# mcu.net
KiCad netlist of a schematic drawn in Altium Designer
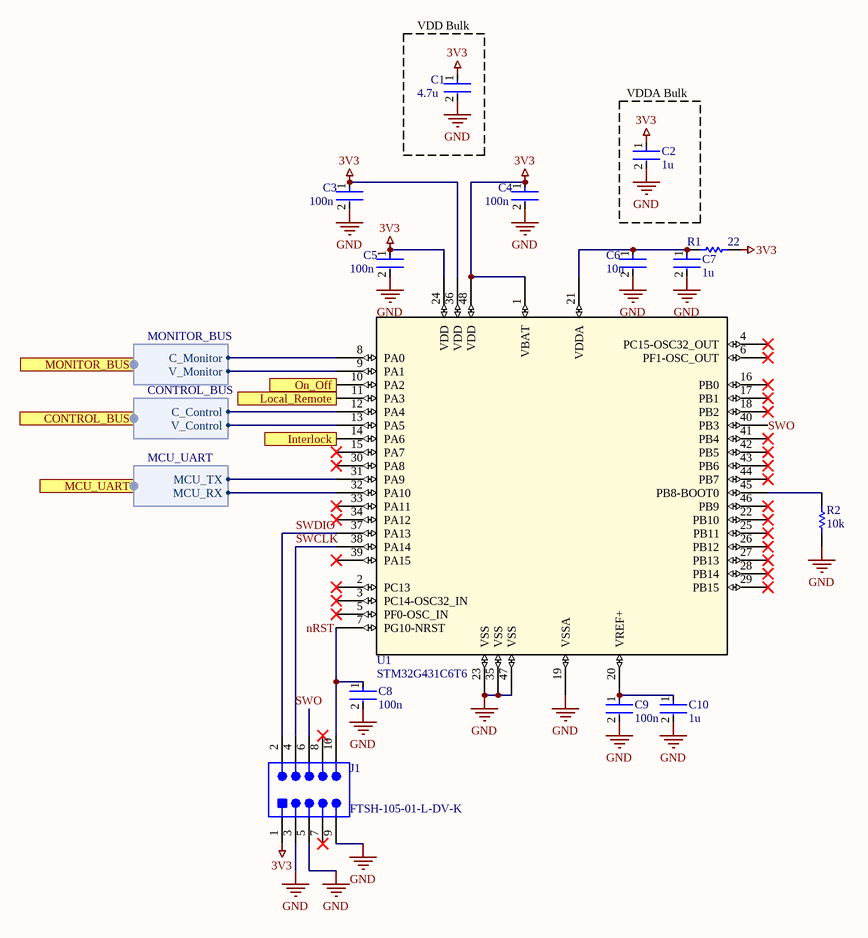
[diagram p0: mcu.SchDoc]

(export (version "E")
  (design (tool "Eeschema 10.0.6"))
  (components
    (comp (ref "C1")
      (value "4.7u")
      (footprint "C_IM 0805")
      (description "Surface Mount Ceramic Multilayer Capacitor 4.7uF 10% X5R 6.3V 0805 Blister T/R")
      (fields
        (field (name "MANUFACTURER") "Yageo Group")
        (field (name "MANUFACTURER PART NUMBER") "CC0805KKX5R5BB475")
      )
      (libsource (lib "Schlib1") (part "CC0805KKX5R5BB475"))
    )
    (comp (ref "C2")
      (value "1u")
      (footprint "C_IM 0603")
      (description "6.3V 1uF X5R ±20% 0603 Multilayer Ceramic Capacitors MLCC - SMD/SMT ROHS")
      (fields
        (field (name "MANUFACTURER") "Yageo Group")
        (field (name "MANUFACTURER PART NUMBER") "CC0603MRX5R5BB105")
      )
      (libsource (lib "Schlib1") (part "CC0603MRX5R5BB105"))
    )
    (comp (ref "C3")
      (value "100n")
      (footprint "C_IM 0603")
      (description "Multilayer Ceramic Capacitor, CC Series, 0.1 - F, - 10%, X7R, 50 V, 0603 [1608 Metric]")
      (fields
        (field (name "MANUFACTURER") "Yageo Group")
        (field (name "MANUFACTURER PART NUMBER") "CC0603KRX7R9BB104")
      )
      (libsource (lib "Schlib1") (part "CC0603KRX7R9BB104"))
    )
    (comp (ref "C4")
      (value "100n")
      (footprint "C_IM 0603")
      (description "Multilayer Ceramic Capacitor, CC Series, 0.1 - F, - 10%, X7R, 50 V, 0603 [1608 Metric]")
      (fields
        (field (name "MANUFACTURER") "Yageo Group")
        (field (name "MANUFACTURER PART NUMBER") "CC0603KRX7R9BB104")
      )
      (libsource (lib "Schlib1") (part "CC0603KRX7R9BB104"))
    )
    (comp (ref "C5")
      (value "100n")
      (footprint "C_IM 0603")
      (description "Multilayer Ceramic Capacitor, CC Series, 0.1 - F, - 10%, X7R, 50 V, 0603 [1608 Metric]")
      (fields
        (field (name "MANUFACTURER") "Yageo Group")
        (field (name "MANUFACTURER PART NUMBER") "CC0603KRX7R9BB104")
      )
      (libsource (lib "Schlib1") (part "CC0603KRX7R9BB104"))
    )
    (comp (ref "C6")
      (value "10n")
      (footprint "C_IM 0603")
      (description "50V 10nF X7R ±20% 0603 Multilayer Ceramic Capacitors MLCC - SMD/SMT ROHS")
      (fields
        (field (name "MANUFACTURER") "Yageo Group")
        (field (name "MANUFACTURER PART NUMBER") "CC0603MRX7R9BB103")
      )
      (libsource (lib "Schlib1") (part "CC0603MRX7R9BB103"))
    )
    (comp (ref "C7")
      (value "1u")
      (footprint "C_IM 0805")
      (description "6.3V 1uF X5R ±10% 0805 Multilayer Ceramic Capacitors MLCC - SMD/SMT ROHS")
      (fields
        (field (name "MANUFACTURER") "Yageo Group")
        (field (name "MANUFACTURER PART NUMBER") "CC0805KKX5R5BB105")
      )
      (libsource (lib "Schlib1") (part "CC0805KKX5R5BB105"))
    )
    (comp (ref "C8")
      (value "100n")
      (footprint "C_IM 0603")
      (description "Multilayer Ceramic Capacitor, CC Series, 0.1 - F, - 10%, X7R, 50 V, 0603 [1608 Metric]")
      (fields
        (field (name "MANUFACTURER") "Yageo Group")
        (field (name "MANUFACTURER PART NUMBER") "CC0603KRX7R9BB104")
      )
      (libsource (lib "Schlib1") (part "CC0603KRX7R9BB104"))
    )
    (comp (ref "C9")
      (value "100n")
      (footprint "C_IM 0603")
      (description "Multilayer Ceramic Capacitor, CC Series, 0.1 - F, - 10%, X7R, 50 V, 0603 [1608 Metric]")
      (fields
        (field (name "MANUFACTURER") "Yageo Group")
        (field (name "MANUFACTURER PART NUMBER") "CC0603KRX7R9BB104")
      )
      (libsource (lib "Schlib1") (part "CC0603KRX7R9BB104"))
    )
    (comp (ref "C10")
      (value "1u")
      (footprint "C_IM 0603")
      (description "6.3V 1uF X5R ±20% 0603 Multilayer Ceramic Capacitors MLCC - SMD/SMT ROHS")
      (fields
        (field (name "MANUFACTURER") "Yageo Group")
        (field (name "MANUFACTURER PART NUMBER") "CC0603MRX5R5BB105")
      )
      (libsource (lib "Schlib1") (part "CC0603MRX5R5BB105"))
    )
    (comp (ref "J1")
      (value "FTSH-105-01-L-DV-K")
      (footprint "FTSH-105-01-L-DV-K")
      (description "CONN HEADER SMD 10POS 1.27MM / Connector Header Surface Mount 10 position 0.050\" (1.27mm)")
      (fields (field (name "MANUFACTURER") "Samtec"))
      (libsource (lib "Schlib1") (part "FTSH-105-01-L-DV-K"))
    )
    (comp (ref "R1")
      (value "22")
      (footprint "R_IM 0805")
      (description "125mW Thick Film Resistors 150V ±100ppm/℃ ±1% 22Ω 0805 Chip Resistor - Surface Mount ROHS")
      (fields
        (field (name "MANUFACTURER") "Yageo Group")
        (field (name "MANUFACTURER PART NUMBER") "RC0805FR-0722RL")
      )
      (libsource (lib "Schlib1") (part "RC0805FR-0722RL"))
    )
    (comp (ref "R2")
      (value "10k")
      (footprint "R_IM 0805")
      (description "Res General Purpose Thick Film 0805 10k Ohm 1% 1/8W ±100ppm/°C Ceramic Paper T/R")
      (fields
        (field (name "MANUFACTURER") "Yageo Group")
        (field (name "MANUFACTURER PART NUMBER") "RC0805FR-0710KL")
      )
      (libsource (lib "Schlib1") (part "RC0805FR-0710KL"))
    )
    (comp (ref "U1")
      (value "STM32G431C6T6")
      (footprint "LQFP48-7x7mm")
      (description "Microcontroller 32-Bit ARM Cortex-M4 RISC 32K-Byte Flash 3.3V 48-Pin LQFP")
      (fields (field (name "MANUFACTURER") "STMicroelectronics"))
      (libsource (lib "Schlib1") (part "STM32G431C6T6"))
    )
  )
  (nets
    (net (code "4") (name "/C_Control") (class "Default")
      (node (ref "U1") (pin "12") (pinfunction "PA4_12") (pintype "bidirectional"))
    )
    (net (code "5") (name "/C_Monitor") (class "Default")
      (node (ref "U1") (pin "8") (pinfunction "PA0_8") (pintype "bidirectional"))
    )
    (net (code "6") (name "/Interlock") (class "Default")
      (node (ref "U1") (pin "14") (pinfunction "PA6_14") (pintype "bidirectional"))
    )
    (net (code "7") (name "/Local_Remote") (class "Default")
      (node (ref "U1") (pin "11") (pinfunction "PA3_11") (pintype "bidirectional"))
    )
    (net (code "8") (name "/MCU_RX") (class "Default")
      (node (ref "U1") (pin "32") (pinfunction "PA10_32") (pintype "bidirectional"))
    )
    (net (code "9") (name "/MCU_TX") (class "Default")
      (node (ref "U1") (pin "31") (pinfunction "PA9_31") (pintype "bidirectional"))
    )
    (net (code "10") (name "/On_Off") (class "Default")
      (node (ref "U1") (pin "10") (pinfunction "PA2_10") (pintype "bidirectional"))
    )
    (net (code "11") (name "/SWCLK") (class "Default")
      (node (ref "J1") (pin "4") (pinfunction "4_4") (pintype "passive"))
      (node (ref "U1") (pin "38") (pinfunction "PA14_38") (pintype "bidirectional"))
    )
    (net (code "12") (name "/SWDIO") (class "Default")
      (node (ref "J1") (pin "2") (pinfunction "2_2") (pintype "passive"))
      (node (ref "U1") (pin "37") (pinfunction "PA13_37") (pintype "bidirectional"))
    )
    (net (code "13") (name "/SWO") (class "Default")
      (node (ref "J1") (pin "6") (pinfunction "6_6") (pintype "passive"))
      (node (ref "U1") (pin "40") (pinfunction "PB3_40") (pintype "bidirectional"))
    )
    (net (code "14") (name "/V_Control") (class "Default")
      (node (ref "U1") (pin "13") (pinfunction "PA5_13") (pintype "bidirectional"))
    )
    (net (code "15") (name "/V_Monitor") (class "Default")
      (node (ref "U1") (pin "9") (pinfunction "PA1_9") (pintype "bidirectional"))
    )
    (net (code "16") (name "/nRST") (class "Default")
      (node (ref "C8") (pin "1") (pinfunction "1_1") (pintype "passive"))
      (node (ref "J1") (pin "10") (pinfunction "10_10") (pintype "passive"))
      (node (ref "U1") (pin "7") (pinfunction "PG10-NRST_7") (pintype "bidirectional"))
    )
    (net (code "20") (name "3V3") (class "Default")
      (node (ref "C1") (pin "1") (pinfunction "1_1") (pintype "passive"))
      (node (ref "C2") (pin "1") (pinfunction "1_1") (pintype "passive"))
      (node (ref "C3") (pin "1") (pinfunction "1_1") (pintype "passive"))
      (node (ref "C4") (pin "1") (pinfunction "1_1") (pintype "passive"))
      (node (ref "C5") (pin "1") (pinfunction "1_1") (pintype "passive"))
      (node (ref "J1") (pin "1") (pinfunction "1_1") (pintype "passive"))
      (node (ref "R1") (pin "2") (pinfunction "2_2") (pintype "passive"))
      (node (ref "U1") (pin "1") (pinfunction "VBAT_1") (pintype "bidirectional"))
      (node (ref "U1") (pin "24") (pinfunction "VDD_24") (pintype "bidirectional"))
      (node (ref "U1") (pin "36") (pinfunction "VDD_36") (pintype "bidirectional"))
      (node (ref "U1") (pin "48") (pinfunction "VDD_48") (pintype "bidirectional"))
    )
    (net (code "21") (name "GND") (class "Default")
      (node (ref "C1") (pin "2") (pinfunction "2_2") (pintype "passive"))
      (node (ref "C10") (pin "2") (pinfunction "2_2") (pintype "passive"))
      (node (ref "C2") (pin "2") (pinfunction "2_2") (pintype "passive"))
      (node (ref "C3") (pin "2") (pinfunction "2_2") (pintype "passive"))
      (node (ref "C4") (pin "2") (pinfunction "2_2") (pintype "passive"))
      (node (ref "C5") (pin "2") (pinfunction "2_2") (pintype "passive"))
      (node (ref "C6") (pin "2") (pinfunction "2_2") (pintype "passive"))
      (node (ref "C7") (pin "2") (pinfunction "2_2") (pintype "passive"))
      (node (ref "C8") (pin "2") (pinfunction "2_2") (pintype "passive"))
      (node (ref "C9") (pin "2") (pinfunction "2_2") (pintype "passive"))
      (node (ref "J1") (pin "3") (pinfunction "3_3") (pintype "passive"))
      (node (ref "J1") (pin "5") (pinfunction "5_5") (pintype "passive"))
      (node (ref "J1") (pin "9") (pinfunction "9_9") (pintype "passive"))
      (node (ref "R2") (pin "1") (pinfunction "1_1") (pintype "passive"))
      (node (ref "U1") (pin "19") (pinfunction "VSSA_19") (pintype "bidirectional"))
      (node (ref "U1") (pin "23") (pinfunction "VSS_23") (pintype "bidirectional"))
      (node (ref "U1") (pin "35") (pinfunction "VSS_35") (pintype "bidirectional"))
      (node (ref "U1") (pin "47") (pinfunction "VSS_47") (pintype "bidirectional"))
    )
    (net (code "22") (name "Net-(U1-PB8-BOOT0)") (class "Default")
      (node (ref "R2") (pin "2") (pinfunction "2_2") (pintype "passive"))
      (node (ref "U1") (pin "45") (pinfunction "PB8-BOOT0_45") (pintype "bidirectional"))
    )
    (net (code "23") (name "Net-(U1-VDDA)") (class "Default")
      (node (ref "C6") (pin "1") (pinfunction "1_1") (pintype "passive"))
      (node (ref "C7") (pin "1") (pinfunction "1_1") (pintype "passive"))
      (node (ref "R1") (pin "1") (pinfunction "1_1") (pintype "passive"))
      (node (ref "U1") (pin "21") (pinfunction "VDDA_21") (pintype "bidirectional"))
    )
    (net (code "24") (name "Net-(U1-VREF+)") (class "Default")
      (node (ref "C10") (pin "1") (pinfunction "1_1") (pintype "passive"))
      (node (ref "C9") (pin "1") (pinfunction "1_1") (pintype "passive"))
      (node (ref "U1") (pin "20") (pinfunction "VREF+_20") (pintype "bidirectional"))
    )
    (net (code "25") (name "unconnected-(J1-Pad7)") (class "Default")
      (node (ref "J1") (pin "7") (pinfunction "7_7") (pintype "passive+no_connect"))
    )
    (net (code "26") (name "unconnected-(J1-Pad8)") (class "Default")
      (node (ref "J1") (pin "8") (pinfunction "8_8") (pintype "passive+no_connect"))
    )
    (net (code "27") (name "unconnected-(U1-PA7-Pad15)") (class "Default")
      (node (ref "U1") (pin "15") (pinfunction "PA7_15") (pintype "bidirectional+no_connect"))
    )
    (net (code "28") (name "unconnected-(U1-PA8-Pad30)") (class "Default")
      (node (ref "U1") (pin "30") (pinfunction "PA8_30") (pintype "bidirectional+no_connect"))
    )
    (net (code "29") (name "unconnected-(U1-PA11-Pad33)") (class "Default")
      (node (ref "U1") (pin "33") (pinfunction "PA11_33") (pintype "bidirectional+no_connect"))
    )
    (net (code "30") (name "unconnected-(U1-PA12-Pad34)") (class "Default")
      (node (ref "U1") (pin "34") (pinfunction "PA12_34") (pintype "bidirectional+no_connect"))
    )
    (net (code "31") (name "unconnected-(U1-PA15-Pad39)") (class "Default")
      (node (ref "U1") (pin "39") (pinfunction "PA15_39") (pintype "bidirectional+no_connect"))
    )
    (net (code "32") (name "unconnected-(U1-PB0-Pad16)") (class "Default")
      (node (ref "U1") (pin "16") (pinfunction "PB0_16") (pintype "bidirectional+no_connect"))
    )
    (net (code "33") (name "unconnected-(U1-PB1-Pad17)") (class "Default")
      (node (ref "U1") (pin "17") (pinfunction "PB1_17") (pintype "bidirectional+no_connect"))
    )
    (net (code "34") (name "unconnected-(U1-PB2-Pad18)") (class "Default")
      (node (ref "U1") (pin "18") (pinfunction "PB2_18") (pintype "bidirectional+no_connect"))
    )
    (net (code "35") (name "unconnected-(U1-PB4-Pad41)") (class "Default")
      (node (ref "U1") (pin "41") (pinfunction "PB4_41") (pintype "bidirectional+no_connect"))
    )
    (net (code "36") (name "unconnected-(U1-PB5-Pad42)") (class "Default")
      (node (ref "U1") (pin "42") (pinfunction "PB5_42") (pintype "bidirectional+no_connect"))
    )
    (net (code "37") (name "unconnected-(U1-PB6-Pad43)") (class "Default")
      (node (ref "U1") (pin "43") (pinfunction "PB6_43") (pintype "bidirectional+no_connect"))
    )
    (net (code "38") (name "unconnected-(U1-PB7-Pad44)") (class "Default")
      (node (ref "U1") (pin "44") (pinfunction "PB7_44") (pintype "bidirectional+no_connect"))
    )
    (net (code "39") (name "unconnected-(U1-PB9-Pad46)") (class "Default")
      (node (ref "U1") (pin "46") (pinfunction "PB9_46") (pintype "bidirectional+no_connect"))
    )
    (net (code "40") (name "unconnected-(U1-PB10-Pad22)") (class "Default")
      (node (ref "U1") (pin "22") (pinfunction "PB10_22") (pintype "bidirectional+no_connect"))
    )
    (net (code "41") (name "unconnected-(U1-PB11-Pad25)") (class "Default")
      (node (ref "U1") (pin "25") (pinfunction "PB11_25") (pintype "bidirectional+no_connect"))
    )
    (net (code "42") (name "unconnected-(U1-PB12-Pad26)") (class "Default")
      (node (ref "U1") (pin "26") (pinfunction "PB12_26") (pintype "bidirectional+no_connect"))
    )
    (net (code "43") (name "unconnected-(U1-PB13-Pad27)") (class "Default")
      (node (ref "U1") (pin "27") (pinfunction "PB13_27") (pintype "bidirectional+no_connect"))
    )
    (net (code "44") (name "unconnected-(U1-PB14-Pad28)") (class "Default")
      (node (ref "U1") (pin "28") (pinfunction "PB14_28") (pintype "bidirectional+no_connect"))
    )
    (net (code "45") (name "unconnected-(U1-PB15-Pad29)") (class "Default")
      (node (ref "U1") (pin "29") (pinfunction "PB15_29") (pintype "bidirectional+no_connect"))
    )
    (net (code "46") (name "unconnected-(U1-PC13-Pad2)") (class "Default")
      (node (ref "U1") (pin "2") (pinfunction "PC13_2") (pintype "bidirectional+no_connect"))
    )
    (net (code "47") (name "unconnected-(U1-PC14-OSC32_IN-Pad3)") (class "Default")
      (node (ref "U1") (pin "3") (pinfunction "PC14-OSC32_IN_3") (pintype "bidirectional+no_connect"))
    )
    (net (code "48") (name "unconnected-(U1-PC15-OSC32_OUT-Pad4)") (class "Default")
      (node (ref "U1") (pin "4") (pinfunction "PC15-OSC32_OUT_4") (pintype "bidirectional+no_connect"))
    )
    (net (code "49") (name "unconnected-(U1-PF0-OSC_IN-Pad5)") (class "Default")
      (node (ref "U1") (pin "5") (pinfunction "PF0-OSC_IN_5") (pintype "bidirectional+no_connect"))
    )
    (net (code "50") (name "unconnected-(U1-PF1-OSC_OUT-Pad6)") (class "Default")
      (node (ref "U1") (pin "6") (pinfunction "PF1-OSC_OUT_6") (pintype "bidirectional+no_connect"))
    )
  )
)
